# dimmerPower7.net
KiCad netlist of a schematic drawn in EAGLE
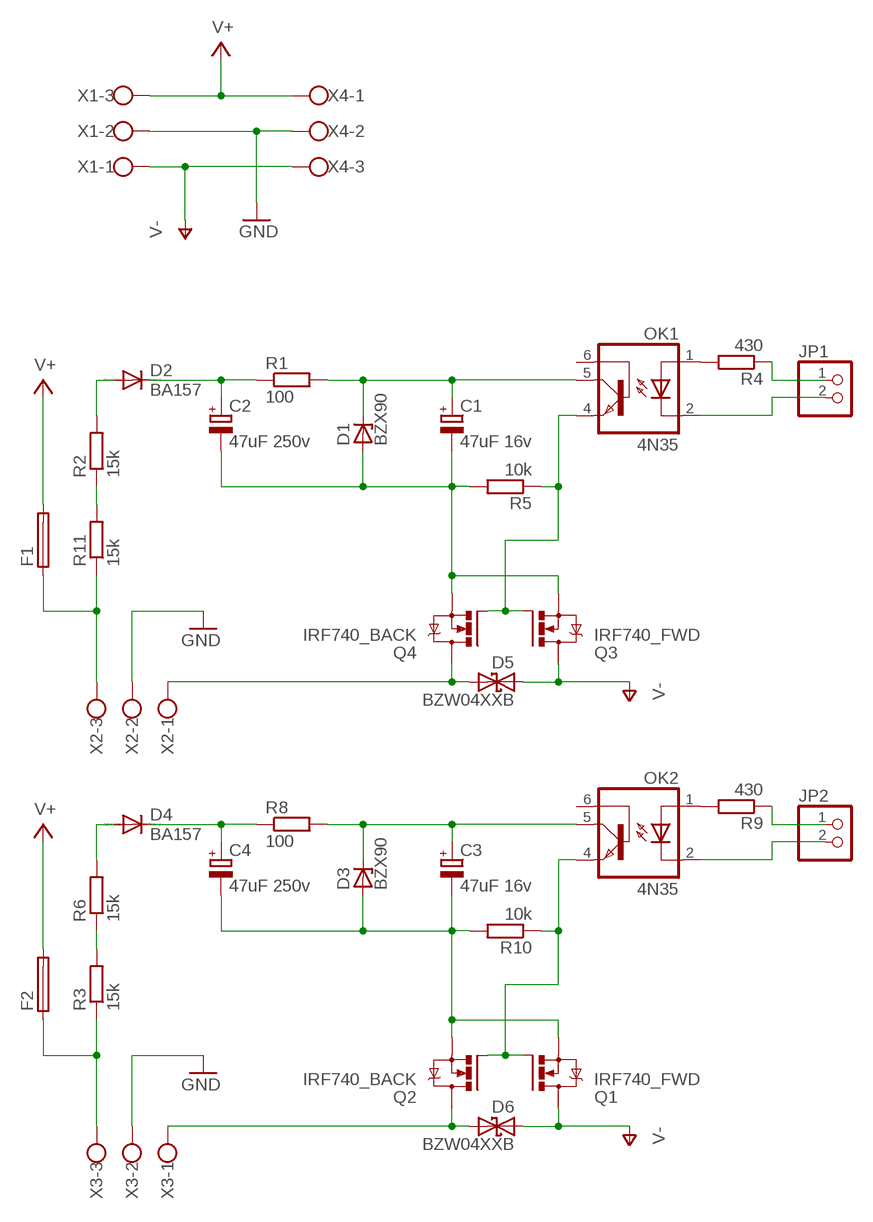
[diagram p0: schematic, sheet 1]

(export (version "E")
  (design (tool "Eeschema 10.0.6"))
  (components
    (comp (ref "C1")
      (value "47uF 16v")
      (footprint "eagle-import:E2,5-6")
      (libsource (lib "eagle-import") (part "CPOL-EUE2.5-6"))
    )
    (comp (ref "C2")
      (value "47uF 250v")
      (footprint "eagle-import:E5-13")
      (libsource (lib "eagle-import") (part "CPOL-EUE5-13"))
    )
    (comp (ref "C3")
      (value "47uF 16v")
      (footprint "eagle-import:E2,5-6")
      (libsource (lib "eagle-import") (part "CPOL-EUE2.5-6"))
    )
    (comp (ref "C4")
      (value "47uF 250v")
      (footprint "eagle-import:E5-13")
      (libsource (lib "eagle-import") (part "CPOL-EUE5-13"))
    )
    (comp (ref "D1")
      (value "BZX90")
      (footprint "eagle-import:DO34Z7")
      (libsource (lib "eagle-import") (part "BZX90"))
    )
    (comp (ref "D2")
      (value "BA157")
      (footprint "eagle-import:P1-10")
      (libsource (lib "eagle-import") (part "BA157"))
    )
    (comp (ref "D3")
      (value "BZX90")
      (footprint "eagle-import:DO34Z7")
      (libsource (lib "eagle-import") (part "BZX90"))
    )
    (comp (ref "D4")
      (value "BA157")
      (footprint "eagle-import:P1-10")
      (libsource (lib "eagle-import") (part "BA157"))
    )
    (comp (ref "D5")
      (value "BZW04XXB")
      (footprint "eagle-import:F126Z12")
      (libsource (lib "eagle-import") (part "BZW04XXB"))
    )
    (comp (ref "D6")
      (value "BZW04XXB")
      (footprint "eagle-import:F126Z12")
      (libsource (lib "eagle-import") (part "BZW04XXB"))
    )
    (comp (ref "F1")
      (value "SH22,5")
      (footprint "eagle-import:SH22,5")
      (fields (field (name "MF") "SCHURTER") (field (name "MPN") "0031.8201"))
      (libsource (lib "eagle-import") (part "SH22,5"))
    )
    (comp (ref "F2")
      (value "SH22,5")
      (footprint "eagle-import:SH22,5")
      (fields (field (name "MF") "SCHURTER") (field (name "MPN") "0031.8201"))
      (libsource (lib "eagle-import") (part "SH22,5"))
    )
    (comp (ref "JP1")
      (value "PINHD-1X2")
      (footprint "eagle-import:1X02")
      (libsource (lib "eagle-import") (part "PINHD-1X2"))
    )
    (comp (ref "JP2")
      (value "PINHD-1X2")
      (footprint "eagle-import:1X02")
      (libsource (lib "eagle-import") (part "PINHD-1X2"))
    )
    (comp (ref "OK1")
      (value "4N35")
      (footprint "eagle-import:DIL06")
      (fields (field (name "MF") "FAIRCHILD SEMICONDUCTOR"))
      (libsource (lib "eagle-import") (part "4N35"))
    )
    (comp (ref "OK2")
      (value "4N35")
      (footprint "eagle-import:DIL06")
      (fields (field (name "MF") "FAIRCHILD SEMICONDUCTOR"))
      (libsource (lib "eagle-import") (part "4N35"))
    )
    (comp (ref "Q1")
      (value "IRF740_FWD")
      (footprint "eagle-import:TO220BV_FWD")
      (libsource (lib "eagle-import") (part "IRF740_FWD"))
    )
    (comp (ref "Q2")
      (value "IRF740_BACK")
      (footprint "eagle-import:TO220BV_BACK")
      (libsource (lib "eagle-import") (part "IRF740_BACK"))
    )
    (comp (ref "Q3")
      (value "IRF740_FWD")
      (footprint "eagle-import:TO220BV_FWD")
      (libsource (lib "eagle-import") (part "IRF740_FWD"))
    )
    (comp (ref "Q4")
      (value "IRF740_BACK")
      (footprint "eagle-import:TO220BV_BACK")
      (libsource (lib "eagle-import") (part "IRF740_BACK"))
    )
    (comp (ref "R1")
      (value "100")
      (footprint "eagle-import:0204_7")
      (libsource (lib "eagle-import") (part "R-EU_0204/7"))
    )
    (comp (ref "R2")
      (value "15k")
      (footprint "eagle-import:P0613_15")
      (libsource (lib "eagle-import") (part "untitled_R-EU_0613/15"))
    )
    (comp (ref "R3")
      (value "15k")
      (footprint "eagle-import:P0613_15")
      (libsource (lib "eagle-import") (part "untitled_R-EU_0613/15"))
    )
    (comp (ref "R4")
      (value "430")
      (footprint "eagle-import:0204_7")
      (libsource (lib "eagle-import") (part "R-EU_0204/7"))
    )
    (comp (ref "R5")
      (value "10k")
      (footprint "eagle-import:0204_7")
      (libsource (lib "eagle-import") (part "R-EU_0204/7"))
    )
    (comp (ref "R6")
      (value "15k")
      (footprint "eagle-import:P0613_15")
      (libsource (lib "eagle-import") (part "untitled_R-EU_0613/15"))
    )
    (comp (ref "R8")
      (value "100")
      (footprint "eagle-import:0204_7")
      (libsource (lib "eagle-import") (part "R-EU_0204/7"))
    )
    (comp (ref "R9")
      (value "430")
      (footprint "eagle-import:0204_7")
      (libsource (lib "eagle-import") (part "R-EU_0204/7"))
    )
    (comp (ref "R10")
      (value "10k")
      (footprint "eagle-import:0204_7")
      (libsource (lib "eagle-import") (part "R-EU_0204/7"))
    )
    (comp (ref "R11")
      (value "15k")
      (footprint "eagle-import:P0613_15")
      (libsource (lib "eagle-import") (part "untitled_R-EU_0613/15"))
    )
    (comp (ref "X1")
      (value "W237-103")
      (footprint "eagle-import:W237-103")
      (fields (field (name "MPN") "237-103"))
      (libsource (lib "eagle-import") (part "W237-103"))
    )
    (comp (ref "X2")
      (value "W237-103")
      (footprint "eagle-import:W237-103")
      (fields (field (name "MPN") "237-103"))
      (libsource (lib "eagle-import") (part "W237-103"))
    )
    (comp (ref "X3")
      (value "W237-103")
      (footprint "eagle-import:W237-103")
      (fields (field (name "MPN") "237-103"))
      (libsource (lib "eagle-import") (part "W237-103"))
    )
    (comp (ref "X4")
      (value "W237-103")
      (footprint "eagle-import:W237-103")
      (fields (field (name "MPN") "237-103"))
      (libsource (lib "eagle-import") (part "W237-103"))
    )
  )
  (nets
    (net (code "1") (name "GND") (class "Default")
      (node (ref "X1") (pin "2") (pinfunction "KL_2") (pintype "passive"))
      (node (ref "X2") (pin "2") (pinfunction "KL_2") (pintype "passive"))
      (node (ref "X3") (pin "2") (pinfunction "KL_2") (pintype "passive"))
      (node (ref "X4") (pin "2") (pinfunction "KL_2") (pintype "passive"))
    )
    (net (code "2") (name "Net-(C1-Pad-)") (class "Default")
      (node (ref "C1") (pin "-") (pinfunction "-_-") (pintype "passive"))
      (node (ref "C2") (pin "-") (pinfunction "-_-") (pintype "passive"))
      (node (ref "D1") (pin "A") (pinfunction "A_A") (pintype "passive"))
      (node (ref "Q3") (pin "S") (pinfunction "S_S") (pintype "passive"))
      (node (ref "Q4") (pin "S") (pinfunction "S_S") (pintype "passive"))
      (node (ref "R5") (pin "2") (pinfunction "2_2") (pintype "passive"))
    )
    (net (code "3") (name "Net-(C2-Pad+)") (class "Default")
      (node (ref "C2") (pin "+") (pinfunction "+_+") (pintype "passive"))
      (node (ref "D2") (pin "C") (pinfunction "C_C") (pintype "passive"))
      (node (ref "R1") (pin "1") (pinfunction "1_1") (pintype "passive"))
    )
    (net (code "4") (name "Net-(C3-Pad-)") (class "Default")
      (node (ref "C3") (pin "-") (pinfunction "-_-") (pintype "passive"))
      (node (ref "C4") (pin "-") (pinfunction "-_-") (pintype "passive"))
      (node (ref "D3") (pin "A") (pinfunction "A_A") (pintype "passive"))
      (node (ref "Q1") (pin "S") (pinfunction "S_S") (pintype "passive"))
      (node (ref "Q2") (pin "S") (pinfunction "S_S") (pintype "passive"))
      (node (ref "R10") (pin "2") (pinfunction "2_2") (pintype "passive"))
    )
    (net (code "5") (name "Net-(C4-Pad+)") (class "Default")
      (node (ref "C4") (pin "+") (pinfunction "+_+") (pintype "passive"))
      (node (ref "D4") (pin "C") (pinfunction "C_C") (pintype "passive"))
      (node (ref "R8") (pin "1") (pinfunction "1_1") (pintype "passive"))
    )
    (net (code "6") (name "Net-(D2-PadA)") (class "Default")
      (node (ref "D2") (pin "A") (pinfunction "A_A") (pintype "passive"))
      (node (ref "R2") (pin "2") (pinfunction "2_2") (pintype "passive"))
    )
    (net (code "7") (name "Net-(D4-PadA)") (class "Default")
      (node (ref "D4") (pin "A") (pinfunction "A_A") (pintype "passive"))
      (node (ref "R6") (pin "2") (pinfunction "2_2") (pintype "passive"))
    )
    (net (code "8") (name "Net-(D5-2)") (class "Default")
      (node (ref "D5") (pin "C") (pinfunction "2_C") (pintype "passive"))
      (node (ref "Q4") (pin "D") (pinfunction "D_D") (pintype "passive"))
      (node (ref "X2") (pin "1") (pinfunction "KL_1") (pintype "passive"))
    )
    (net (code "9") (name "Net-(D6-2)") (class "Default")
      (node (ref "D6") (pin "C") (pinfunction "2_C") (pintype "passive"))
      (node (ref "Q2") (pin "D") (pinfunction "D_D") (pintype "passive"))
      (node (ref "X3") (pin "1") (pinfunction "KL_1") (pintype "passive"))
    )
    (net (code "10") (name "Net-(JP1-Pad1)") (class "Default")
      (node (ref "JP1") (pin "1") (pinfunction "1_1") (pintype "passive"))
      (node (ref "R4") (pin "1") (pinfunction "1_1") (pintype "passive"))
    )
    (net (code "11") (name "Net-(JP2-Pad1)") (class "Default")
      (node (ref "JP2") (pin "1") (pinfunction "1_1") (pintype "passive"))
      (node (ref "R9") (pin "1") (pinfunction "1_1") (pintype "passive"))
    )
    (net (code "12") (name "Net-(OK1-A)") (class "Default")
      (node (ref "OK1") (pin "1") (pinfunction "A_1") (pintype "passive"))
      (node (ref "R4") (pin "2") (pinfunction "2_2") (pintype "passive"))
    )
    (net (code "13") (name "Net-(OK1-C)") (class "Default")
      (node (ref "JP1") (pin "2") (pinfunction "2_2") (pintype "passive"))
      (node (ref "OK1") (pin "2") (pinfunction "C_2") (pintype "passive"))
    )
    (net (code "14") (name "Net-(OK1-COL)") (class "Default")
      (node (ref "C1") (pin "+") (pinfunction "+_+") (pintype "passive"))
      (node (ref "D1") (pin "C") (pinfunction "C_C") (pintype "passive"))
      (node (ref "OK1") (pin "5") (pinfunction "COL_5") (pintype "passive"))
      (node (ref "R1") (pin "2") (pinfunction "2_2") (pintype "passive"))
    )
    (net (code "15") (name "Net-(OK1-EMI)") (class "Default")
      (node (ref "OK1") (pin "4") (pinfunction "EMI_4") (pintype "passive"))
      (node (ref "Q3") (pin "G") (pinfunction "G_G") (pintype "passive"))
      (node (ref "Q4") (pin "G") (pinfunction "G_G") (pintype "passive"))
      (node (ref "R5") (pin "1") (pinfunction "1_1") (pintype "passive"))
    )
    (net (code "16") (name "Net-(OK2-A)") (class "Default")
      (node (ref "OK2") (pin "1") (pinfunction "A_1") (pintype "passive"))
      (node (ref "R9") (pin "2") (pinfunction "2_2") (pintype "passive"))
    )
    (net (code "17") (name "Net-(OK2-C)") (class "Default")
      (node (ref "JP2") (pin "2") (pinfunction "2_2") (pintype "passive"))
      (node (ref "OK2") (pin "2") (pinfunction "C_2") (pintype "passive"))
    )
    (net (code "18") (name "Net-(OK2-COL)") (class "Default")
      (node (ref "C3") (pin "+") (pinfunction "+_+") (pintype "passive"))
      (node (ref "D3") (pin "C") (pinfunction "C_C") (pintype "passive"))
      (node (ref "OK2") (pin "5") (pinfunction "COL_5") (pintype "passive"))
      (node (ref "R8") (pin "2") (pinfunction "2_2") (pintype "passive"))
    )
    (net (code "19") (name "Net-(OK2-EMI)") (class "Default")
      (node (ref "OK2") (pin "4") (pinfunction "EMI_4") (pintype "passive"))
      (node (ref "Q1") (pin "G") (pinfunction "G_G") (pintype "passive"))
      (node (ref "Q2") (pin "G") (pinfunction "G_G") (pintype "passive"))
      (node (ref "R10") (pin "1") (pinfunction "1_1") (pintype "passive"))
    )
    (net (code "20") (name "Net-(R3-Pad2)") (class "Default")
      (node (ref "R3") (pin "2") (pinfunction "2_2") (pintype "passive"))
      (node (ref "R6") (pin "1") (pinfunction "1_1") (pintype "passive"))
    )
    (net (code "21") (name "Net-(R11-Pad2)") (class "Default")
      (node (ref "R11") (pin "2") (pinfunction "2_2") (pintype "passive"))
      (node (ref "R2") (pin "1") (pinfunction "1_1") (pintype "passive"))
    )
    (net (code "22") (name "Net-(X2C-KL)") (class "Default")
      (node (ref "F1") (pin "1") (pinfunction "1_1") (pintype "passive"))
      (node (ref "R11") (pin "1") (pinfunction "1_1") (pintype "passive"))
      (node (ref "X2") (pin "3") (pinfunction "KL_3") (pintype "passive"))
    )
    (net (code "23") (name "Net-(X3C-KL)") (class "Default")
      (node (ref "F2") (pin "1") (pinfunction "1_1") (pintype "passive"))
      (node (ref "R3") (pin "1") (pinfunction "1_1") (pintype "passive"))
      (node (ref "X3") (pin "3") (pinfunction "KL_3") (pintype "passive"))
    )
    (net (code "24") (name "V+") (class "Default")
      (node (ref "F1") (pin "2") (pinfunction "2_2") (pintype "passive"))
      (node (ref "F2") (pin "2") (pinfunction "2_2") (pintype "passive"))
      (node (ref "X1") (pin "3") (pinfunction "KL_3") (pintype "passive"))
      (node (ref "X4") (pin "1") (pinfunction "KL_1") (pintype "passive"))
    )
    (net (code "25") (name "V-") (class "Default")
      (node (ref "D5") (pin "A") (pinfunction "1_A") (pintype "passive"))
      (node (ref "D6") (pin "A") (pinfunction "1_A") (pintype "passive"))
      (node (ref "Q1") (pin "D") (pinfunction "D_D") (pintype "passive"))
      (node (ref "Q3") (pin "D") (pinfunction "D_D") (pintype "passive"))
      (node (ref "X1") (pin "1") (pinfunction "KL_1") (pintype "passive"))
      (node (ref "X4") (pin "3") (pinfunction "KL_3") (pintype "passive"))
    )
    (net (code "26") (name "unconnected-(OK1-BAS-Pad6)") (class "Default")
      (node (ref "OK1") (pin "6") (pinfunction "BAS_6") (pintype "passive"))
    )
    (net (code "27") (name "unconnected-(OK2-BAS-Pad6)") (class "Default")
      (node (ref "OK2") (pin "6") (pinfunction "BAS_6") (pintype "passive"))
    )
  )
)
